# GSH_Bed_V1_0.net
KiCad netlist of a schematic drawn in Altium Designer
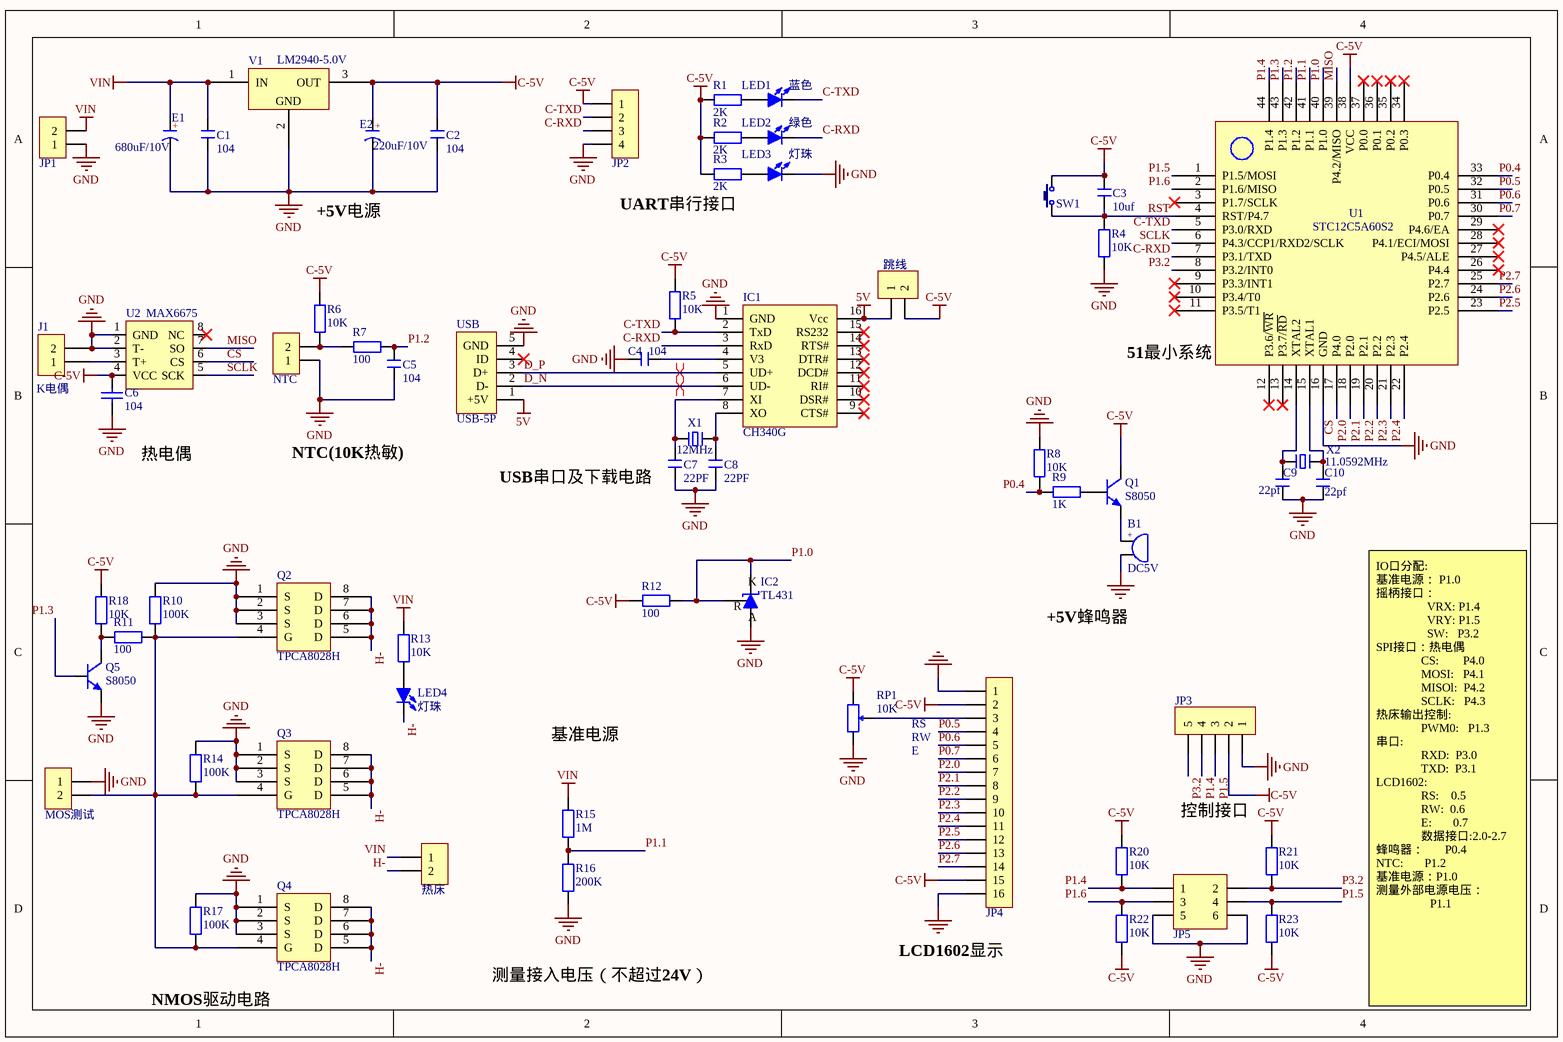
[diagram p0: GSH_Bed_V1.0.SchDoc]

(export (version "E")
  (design (tool "Eeschema 10.0.6"))
  (components
    (comp (ref "B1")
      (value "DC5V")
      (footprint "Buzzer")
      (description "蜂鸣器")
      (fields (field (name "版权归属") "源创客"))
      (libsource (lib "未分类器件") (part "BEEP"))
    )
    (comp (ref "C1")
      (value "104")
      (footprint "C 0805")
      (description "无极性贴片电容")
      (fields (field (name "版权归属") "源创客"))
      (libsource (lib "电阻-电容-电感") (part "C"))
    )
    (comp (ref "C2")
      (value "104")
      (footprint "C 0805")
      (description "无极性贴片电容")
      (fields (field (name "版权归属") "源创客"))
      (libsource (lib "电阻-电容-电感") (part "C"))
    )
    (comp (ref "C3")
      (value "10uf")
      (footprint "C 0603")
      (description "无极性贴片电容")
      (fields (field (name "版权归属") "源创客"))
      (libsource (lib "电阻-电容-电感") (part "C"))
    )
    (comp (ref "C4")
      (value "104")
      (footprint "C 0603")
      (description "无极性贴片电容")
      (fields (field (name "版权归属") "源创客"))
      (libsource (lib "电阻-电容-电感") (part "C"))
    )
    (comp (ref "C5")
      (value "104")
      (footprint "C 0603")
      (description "无极性贴片电容")
      (fields (field (name "版权归属") "源创客"))
      (libsource (lib "电阻-电容-电感") (part "C"))
    )
    (comp (ref "C6")
      (value "104")
      (footprint "C 0603")
      (description "Capacitor")
      (fields (field (name "PUBLISHER") "Altium Limited"))
      (libsource (lib "Miscellaneous Devices") (part "Cap"))
    )
    (comp (ref "C7")
      (value "22PF")
      (footprint "C 0603")
      (description "无极性贴片电容")
      (fields (field (name "版权归属") "源创客"))
      (libsource (lib "电阻-电容-电感") (part "C"))
    )
    (comp (ref "C8")
      (value "22PF")
      (footprint "C 0603")
      (description "无极性贴片电容")
      (fields (field (name "版权归属") "源创客"))
      (libsource (lib "电阻-电容-电感") (part "C"))
    )
    (comp (ref "C9")
      (value "22pf")
      (footprint "C 0603")
      (description "无极性贴片电容")
      (fields (field (name "版权归属") "源创客"))
      (libsource (lib "电阻-电容-电感") (part "C"))
    )
    (comp (ref "C10")
      (value "22pf")
      (footprint "C 0603")
      (description "无极性贴片电容")
      (fields (field (name "版权归属") "源创客"))
      (libsource (lib "电阻-电容-电感") (part "C"))
    )
    (comp (ref "E1")
      (value "680uF/10V")
      (footprint "CM F(10*10.2)")
      (description "贴片电解电容")
      (fields (field (name "版权归属") "源创客"))
      (libsource (lib "电阻-电容-电感") (part "C-CM"))
    )
    (comp (ref "E2")
      (value "220uF/10V")
      (footprint "CM D(6.3*5.4)")
      (description "贴片电解电容")
      (fields (field (name "版权归属") "源创客"))
      (libsource (lib "电阻-电容-电感") (part "C-CM"))
    )
    (comp (ref "IC1")
      (value "CH340G")
      (footprint "SOP16_N")
      (description "串口转USB")
      (fields (field (name "版权归属") "源创客"))
      (libsource (lib "IC芯片") (part "CH340G"))
    )
    (comp (ref "IC2")
      (value "TL431")
      (footprint "SOT23-3L")
      (description "可调基准稳压芯片")
      (fields (field (name "版权归属") "源创客"))
      (libsource (lib "1.3   - 电源类芯片") (part "TL431-ID"))
    )
    (comp (ref "J1")
      (value "K电偶")
      (footprint "HDR-1x2")
      (description "Connector")
      (libsource (lib "lihong_sch") (part "CON2"))
    )
    (comp (ref "JP1")
      (value "HDR-1X2")
      (footprint "KF2EDGK5.0-2P")
      (description "2P接插件")
      (fields (field (name "版权归属") "源创客"))
      (libsource (lib "") (part "Header 2_2"))
    )
    (comp (ref "JP2")
      (value "HDR-1X4")
      (footprint "HDR-1X4")
      (description "4P接插件")
      (fields (field (name "版权归属") "源创客"))
      (libsource (lib "接插件") (part "Header 4"))
    )
    (comp (ref "JP3")
      (value "HDR-1X5")
      (footprint "XH2.54-5P")
      (description "5P接插件")
      (fields (field (name "版权归属") "源创客"))
      (libsource (lib "接插件") (part "Header 5"))
    )
    (comp (ref "JP4")
      (value "HDR-1X16")
      (footprint "LCD-1602")
      (description "16P接插件")
      (fields (field (name "版权归属") "源创客"))
      (libsource (lib "接插件") (part "Header 16"))
    )
    (comp (ref "JP5")
      (value "Header3X2")
      (footprint "HDR-3X2")
      (description "3*2P接插件")
      (fields (field (name "版权归属") "源创客"))
      (libsource (lib "接插件") (part "Header 3X2"))
    )
    (comp (ref "LED1")
      (value "蓝色")
      (footprint "LED 0603B")
      (description "贴片LED")
      (fields (field (name "版权归属") "源创客"))
      (libsource (lib "LED") (part "LED-SMD"))
    )
    (comp (ref "LED2")
      (value "绿色")
      (footprint "LED 0603G")
      (description "贴片LED")
      (fields (field (name "版权归属") "源创客"))
      (libsource (lib "LED") (part "LED-SMD"))
    )
    (comp (ref "LED3")
      (value "灯珠")
      (footprint "LED 3MM-R")
      (description "3mm-LED")
      (fields (field (name "版权归属") "源创客"))
      (libsource (lib "LED") (part "LED-SMD"))
    )
    (comp (ref "LED4")
      (value "灯珠")
      (footprint "LED 3MM-R")
      (description "3mm-LED")
      (fields (field (name "版权归属") "源创客"))
      (libsource (lib "LED") (part "LED-SMD"))
    )
    (comp (ref "MOS测试")
      (value "HDR-1X2")
      (footprint "HDR-1X2")
      (description "2P接插件")
      (fields (field (name "版权归属") "源创客"))
      (libsource (lib "接插件") (part "Header 2"))
    )
    (comp (ref "NTC")
      (value "HDR-1X2")
      (footprint "XH2.54-2P")
      (description "2P接插件")
      (fields (field (name "版权归属") "源创客"))
      (libsource (lib "") (part "Header 2_2"))
    )
    (comp (ref "Q1")
      (value "S8050")
      (footprint "SOT23-3N")
      (description "高频放大-NPN型")
      (fields (field (name "版权归属") "源创客"))
      (libsource (lib "三极管") (part "8050-SMD"))
    )
    (comp (ref "Q2")
      (value "TPCA8028H")
      (footprint "MOS")
      (description "n-mos")
      (libsource (lib "stc12c5a60s2") (part "AON7544"))
    )
    (comp (ref "Q3")
      (value "TPCA8028H")
      (footprint "MOS")
      (description "n-mos")
      (libsource (lib "stc12c5a60s2") (part "AON7544"))
    )
    (comp (ref "Q4")
      (value "TPCA8028H")
      (footprint "MOS")
      (description "n-mos")
      (libsource (lib "stc12c5a60s2") (part "AON7544"))
    )
    (comp (ref "Q5")
      (value "S8050")
      (footprint "SOT23-3N")
      (description "高频放大-NPN型")
      (fields (field (name "版权归属") "源创客"))
      (libsource (lib "三极管") (part "8050-SMD"))
    )
    (comp (ref "R1")
      (value "2K")
      (footprint "R 0603-HP")
      (description "贴片电阻")
      (fields (field (name "版权归属") "源创客"))
      (libsource (lib "电阻-电容-电感") (part "R"))
    )
    (comp (ref "R2")
      (value "2K")
      (footprint "R 0603-HP")
      (description "贴片电阻")
      (fields (field (name "版权归属") "源创客"))
      (libsource (lib "电阻-电容-电感") (part "R"))
    )
    (comp (ref "R3")
      (value "2K")
      (footprint "R 0603-HP")
      (description "贴片电阻")
      (fields (field (name "版权归属") "源创客"))
      (libsource (lib "电阻-电容-电感") (part "R"))
    )
    (comp (ref "R4")
      (value "10K")
      (footprint "R 0603-HP")
      (description "贴片电阻")
      (fields (field (name "版权归属") "源创客"))
      (libsource (lib "电阻-电容-电感") (part "R"))
    )
    (comp (ref "R5")
      (value "10K")
      (footprint "R 0603-HP")
      (description "贴片电阻")
      (fields (field (name "版权归属") "源创客"))
      (libsource (lib "电阻-电容-电感") (part "R"))
    )
    (comp (ref "R6")
      (value "10K")
      (footprint "R 0603-HP")
      (description "贴片电阻")
      (fields (field (name "版权归属") "源创客"))
      (libsource (lib "电阻-电容-电感") (part "R"))
    )
    (comp (ref "R7")
      (value "100")
      (footprint "R 0603-HP")
      (description "贴片电阻")
      (fields (field (name "版权归属") "源创客"))
      (libsource (lib "电阻-电容-电感") (part "R"))
    )
    (comp (ref "R8")
      (value "10K")
      (footprint "R 0603-HP")
      (description "贴片电阻")
      (fields (field (name "版权归属") "源创客"))
      (libsource (lib "电阻-电容-电感") (part "R"))
    )
    (comp (ref "R9")
      (value "1K")
      (footprint "R 0603-HP")
      (description "贴片电阻")
      (fields (field (name "版权归属") "源创客"))
      (libsource (lib "电阻-电容-电感") (part "R"))
    )
    (comp (ref "R10")
      (value "100K")
      (footprint "R 0603-HP")
      (description "贴片电阻")
      (fields (field (name "版权归属") "源创客"))
      (libsource (lib "电阻-电容-电感") (part "R"))
    )
    (comp (ref "R11")
      (value "100")
      (footprint "R 0603-HP")
      (description "贴片电阻")
      (fields (field (name "版权归属") "源创客"))
      (libsource (lib "电阻-电容-电感") (part "R"))
    )
    (comp (ref "R12")
      (value "100")
      (footprint "R 0603-HP")
      (description "贴片电阻")
      (fields (field (name "版权归属") "源创客"))
      (libsource (lib "电阻-电容-电感") (part "R"))
    )
    (comp (ref "R13")
      (value "10K")
      (footprint "R 0603-HP")
      (description "贴片电阻")
      (fields (field (name "版权归属") "源创客"))
      (libsource (lib "电阻-电容-电感") (part "R"))
    )
    (comp (ref "R14")
      (value "100K")
      (footprint "R 0603-HP")
      (description "贴片电阻")
      (fields (field (name "版权归属") "源创客"))
      (libsource (lib "电阻-电容-电感") (part "R"))
    )
    (comp (ref "R15")
      (value "1M")
      (footprint "R 0603-HP")
      (description "贴片电阻")
      (fields (field (name "版权归属") "源创客"))
      (libsource (lib "电阻-电容-电感") (part "R"))
    )
    (comp (ref "R16")
      (value "200K")
      (footprint "R 0603-HP")
      (description "贴片电阻")
      (fields (field (name "版权归属") "源创客"))
      (libsource (lib "电阻-电容-电感") (part "R"))
    )
    (comp (ref "R17")
      (value "100K")
      (footprint "R 0603-HP")
      (description "贴片电阻")
      (fields (field (name "版权归属") "源创客"))
      (libsource (lib "电阻-电容-电感") (part "R"))
    )
    (comp (ref "R18")
      (value "10K")
      (footprint "R 0603-HP")
      (description "贴片电阻")
      (fields (field (name "版权归属") "源创客"))
      (libsource (lib "电阻-电容-电感") (part "R"))
    )
    (comp (ref "R20")
      (value "10K")
      (footprint "R 0603-HP")
      (description "贴片电阻")
      (fields (field (name "版权归属") "源创客"))
      (libsource (lib "电阻-电容-电感") (part "R"))
    )
    (comp (ref "R21")
      (value "10K")
      (footprint "R 0603-HP")
      (description "贴片电阻")
      (fields (field (name "版权归属") "源创客"))
      (libsource (lib "电阻-电容-电感") (part "R"))
    )
    (comp (ref "R22")
      (value "10K")
      (footprint "R 0603-HP")
      (description "贴片电阻")
      (fields (field (name "版权归属") "源创客"))
      (libsource (lib "电阻-电容-电感") (part "R"))
    )
    (comp (ref "R23")
      (value "10K")
      (footprint "R 0603-HP")
      (description "贴片电阻")
      (fields (field (name "版权归属") "源创客"))
      (libsource (lib "电阻-电容-电感") (part "R"))
    )
    (comp (ref "RP1")
      (value "10K")
      (footprint "RM065")
      (description "插件单联电位器")
      (fields (field (name "版权归属") "源创客"))
      (libsource (lib "电阻-电容-电感") (part "RP-ID"))
    )
    (comp (ref "SW1")
      (value "3x6x5")
      (footprint "TSW SMD-3*6*2.5")
      (description "3x6轻触开关")
      (fields (field (name "版权归属") "源创客"))
      (libsource (lib "按键-开关") (part "TSW 3x6"))
    )
    (comp (ref "U1")
      (value "STC12C5A60S2")
      (footprint "LQFP44 10X10_L")
      (libsource (lib "stc12c5a60s2") (part "U?"))
    )
    (comp (ref "U2")
      (value "MAX6675")
      (footprint "SOP8_L")
      (description "K电偶转换")
      (libsource (lib "lihong_IC") (part "MAX6675"))
    )
    (comp (ref "USB")
      (value "USB-5P")
      (footprint "USB-MICRO_A")
      (description "微型USB母座")
      (fields (field (name "版权归属") "源创客"))
      (libsource (lib "接口类") (part "USB-5P"))
    )
    (comp (ref "V1")
      (value "LM2940-5.0V")
      (footprint "TO252")
      (description "5V稳压芯片")
      (fields (field (name "版权归属") "源创客"))
      (libsource (lib "IC芯片") (part "LM2940"))
    )
    (comp (ref "X1")
      (value "12MHz")
      (footprint "XTAL-49S DIP")
      (description "2脚晶振")
      (fields (field (name "版权归属") "源创客"))
      (libsource (lib "保险丝-晶振") (part "XTAL-2"))
    )
    (comp (ref "X2")
      (value "11.0592MHz")
      (footprint "XTAL-49S DIP")
      (description "2脚晶振")
      (fields (field (name "版权归属") "源创客"))
      (libsource (lib "保险丝-晶振") (part "XTAL-2"))
    )
    (comp (ref "热床")
      (value "HDR-1X2")
      (footprint "KF2EDGK5.0-2P")
      (description "2P接插件")
      (fields (field (name "版权归属") "源创客"))
      (libsource (lib "") (part "Header 2_1"))
    )
    (comp (ref "跳线")
      (value "HDR-1X2")
      (footprint "HDR-1X2")
      (description "2P接插件")
      (fields (field (name "版权归属") "源创客"))
      (libsource (lib "") (part "Header 2_3"))
    )
  )
  (nets
    (net (code "1") (name "/C-RXD") (class "Default")
      (node (ref "IC1") (pin "3") (pinfunction "RxD_3") (pintype "passive"))
      (node (ref "JP2") (pin "3") (pinfunction "3_3") (pintype "passive"))
      (node (ref "LED2") (pin "2") (pinfunction "K_2") (pintype "passive"))
      (node (ref "U1") (pin "7") (pinfunction "P3.1/TXD_7") (pintype "passive"))
    )
    (net (code "2") (name "/C-TXD") (class "Default")
      (node (ref "IC1") (pin "2") (pinfunction "TxD_2") (pintype "passive"))
      (node (ref "JP2") (pin "2") (pinfunction "2_2") (pintype "passive"))
      (node (ref "LED1") (pin "2") (pinfunction "K_2") (pintype "passive"))
      (node (ref "R5") (pin "1") (pinfunction "1_1") (pintype "passive"))
      (node (ref "U1") (pin "5") (pinfunction "P3.0/RXD_5") (pintype "passive"))
    )
    (net (code "3") (name "/CS") (class "Default")
      (node (ref "U1") (pin "17") (pinfunction "P4.0_17") (pintype "passive"))
      (node (ref "U2") (pin "6") (pinfunction "CS_6") (pintype "passive"))
    )
    (net (code "4") (name "/D_N") (class "Default")
      (node (ref "IC1") (pin "6") (pinfunction "UD-_6") (pintype "passive"))
      (node (ref "USB") (pin "2") (pinfunction "D-_2") (pintype "passive"))
    )
    (net (code "5") (name "/D_P") (class "Default")
      (node (ref "IC1") (pin "5") (pinfunction "UD+_5") (pintype "passive"))
      (node (ref "USB") (pin "3") (pinfunction "D+_3") (pintype "passive"))
    )
    (net (code "6") (name "/H-") (class "Default")
      (node (ref "LED4") (pin "2") (pinfunction "K_2") (pintype "passive"))
      (node (ref "Q2") (pin "5") (pinfunction "D_5") (pintype "passive"))
      (node (ref "Q2") (pin "6") (pinfunction "D_6") (pintype "passive"))
      (node (ref "Q2") (pin "7") (pinfunction "D_7") (pintype "passive"))
      (node (ref "Q2") (pin "8") (pinfunction "D_8") (pintype "passive"))
      (node (ref "Q3") (pin "5") (pinfunction "D_5") (pintype "passive"))
      (node (ref "Q3") (pin "6") (pinfunction "D_6") (pintype "passive"))
      (node (ref "Q3") (pin "7") (pinfunction "D_7") (pintype "passive"))
      (node (ref "Q3") (pin "8") (pinfunction "D_8") (pintype "passive"))
      (node (ref "Q4") (pin "5") (pinfunction "D_5") (pintype "passive"))
      (node (ref "Q4") (pin "6") (pinfunction "D_6") (pintype "passive"))
      (node (ref "Q4") (pin "7") (pinfunction "D_7") (pintype "passive"))
      (node (ref "Q4") (pin "8") (pinfunction "D_8") (pintype "passive"))
      (node (ref "热床") (pin "2") (pinfunction "2_2") (pintype "passive"))
    )
    (net (code "7") (name "/MISO") (class "Default")
      (node (ref "U1") (pin "39") (pinfunction "P4.2/MISO_39") (pintype "passive"))
      (node (ref "U2") (pin "7") (pinfunction "SO_7") (pintype "passive"))
    )
    (net (code "8") (name "/P0.4") (class "Default")
      (node (ref "R8") (pin "2") (pinfunction "2_2") (pintype "passive"))
      (node (ref "R9") (pin "1") (pinfunction "1_1") (pintype "passive"))
      (node (ref "U1") (pin "33") (pinfunction "P0.4_33") (pintype "passive"))
    )
    (net (code "9") (name "/P0.5") (class "Default")
      (node (ref "JP4") (pin "4") (pinfunction "4_4") (pintype "passive"))
      (node (ref "U1") (pin "32") (pinfunction "P0.5_32") (pintype "passive"))
    )
    (net (code "10") (name "/P0.6") (class "Default")
      (node (ref "JP4") (pin "5") (pinfunction "5_5") (pintype "passive"))
      (node (ref "U1") (pin "31") (pinfunction "P0.6_31") (pintype "passive"))
    )
    (net (code "11") (name "/P0.7") (class "Default")
      (node (ref "JP4") (pin "6") (pinfunction "6_6") (pintype "passive"))
      (node (ref "U1") (pin "30") (pinfunction "P0.7_30") (pintype "passive"))
    )
    (net (code "12") (name "/P1.0") (class "Default")
      (node (ref "IC2") (pin "1") (pinfunction "R_1") (pintype "passive"))
      (node (ref "IC2") (pin "2") (pinfunction "K_2") (pintype "passive"))
      (node (ref "R12") (pin "1") (pinfunction "1_1") (pintype "passive"))
      (node (ref "U1") (pin "40") (pinfunction "P1.0_40") (pintype "passive"))
    )
    (net (code "13") (name "/P1.1") (class "Default")
      (node (ref "R15") (pin "1") (pinfunction "1_1") (pintype "passive"))
      (node (ref "R16") (pin "2") (pinfunction "2_2") (pintype "passive"))
      (node (ref "U1") (pin "41") (pinfunction "P1.1_41") (pintype "passive"))
    )
    (net (code "14") (name "/P1.2") (class "Default")
      (node (ref "C5") (pin "2") (pinfunction "2_2") (pintype "passive"))
      (node (ref "R7") (pin "1") (pinfunction "1_1") (pintype "passive"))
      (node (ref "U1") (pin "42") (pinfunction "P1.2_42") (pintype "passive"))
    )
    (net (code "15") (name "/P1.3") (class "Default")
      (node (ref "Q5") (pin "1") (pinfunction "B_1") (pintype "passive"))
      (node (ref "U1") (pin "43") (pinfunction "P1.3_43") (pintype "passive"))
    )
    (net (code "16") (name "/P1.4") (class "Default")
      (node (ref "JP3") (pin "4") (pinfunction "4_4") (pintype "passive"))
      (node (ref "JP5") (pin "1") (pinfunction "1_1") (pintype "passive"))
      (node (ref "R20") (pin "1") (pinfunction "1_1") (pintype "passive"))
      (node (ref "U1") (pin "44") (pinfunction "P1.4_44") (pintype "passive"))
    )
    (net (code "17") (name "/P1.5") (class "Default")
      (node (ref "JP3") (pin "3") (pinfunction "3_3") (pintype "passive"))
      (node (ref "JP5") (pin "4") (pinfunction "4_4") (pintype "passive"))
      (node (ref "R23") (pin "2") (pinfunction "2_2") (pintype "passive"))
      (node (ref "U1") (pin "1") (pinfunction "P1.5/MOSI_1") (pintype "passive"))
    )
    (net (code "18") (name "/P1.6") (class "Default")
      (node (ref "JP5") (pin "3") (pinfunction "3_3") (pintype "passive"))
      (node (ref "R22") (pin "2") (pinfunction "2_2") (pintype "passive"))
      (node (ref "U1") (pin "2") (pinfunction "P1.6/MISO_2") (pintype "passive"))
    )
    (net (code "19") (name "/P2.0") (class "Default")
      (node (ref "JP4") (pin "7") (pinfunction "7_7") (pintype "passive"))
      (node (ref "U1") (pin "18") (pinfunction "P2.0_18") (pintype "passive"))
    )
    (net (code "20") (name "/P2.1") (class "Default")
      (node (ref "JP4") (pin "8") (pinfunction "8_8") (pintype "passive"))
      (node (ref "U1") (pin "19") (pinfunction "P2.1_19") (pintype "passive"))
    )
    (net (code "21") (name "/P2.2") (class "Default")
      (node (ref "JP4") (pin "9") (pinfunction "9_9") (pintype "passive"))
      (node (ref "U1") (pin "20") (pinfunction "P2.2_20") (pintype "passive"))
    )
    (net (code "22") (name "/P2.3") (class "Default")
      (node (ref "JP4") (pin "10") (pinfunction "10_10") (pintype "passive"))
      (node (ref "U1") (pin "21") (pinfunction "P2.3_21") (pintype "passive"))
    )
    (net (code "23") (name "/P2.4") (class "Default")
      (node (ref "JP4") (pin "11") (pinfunction "11_11") (pintype "passive"))
      (node (ref "U1") (pin "22") (pinfunction "P2.4_22") (pintype "passive"))
    )
    (net (code "24") (name "/P2.5") (class "Default")
      (node (ref "JP4") (pin "12") (pinfunction "12_12") (pintype "passive"))
      (node (ref "U1") (pin "23") (pinfunction "P2.5_23") (pintype "passive"))
    )
    (net (code "25") (name "/P2.6") (class "Default")
      (node (ref "JP4") (pin "13") (pinfunction "13_13") (pintype "passive"))
      (node (ref "U1") (pin "24") (pinfunction "P2.6_24") (pintype "passive"))
    )
    (net (code "26") (name "/P2.7") (class "Default")
      (node (ref "JP4") (pin "14") (pinfunction "14_14") (pintype "passive"))
      (node (ref "U1") (pin "25") (pinfunction "P2.7_25") (pintype "passive"))
    )
    (net (code "27") (name "/P3.2") (class "Default")
      (node (ref "JP3") (pin "5") (pinfunction "5_5") (pintype "passive"))
      (node (ref "JP5") (pin "2") (pinfunction "2_2") (pintype "passive"))
      (node (ref "R21") (pin "1") (pinfunction "1_1") (pintype "passive"))
      (node (ref "U1") (pin "8") (pinfunction "P3.2/INT0_8") (pintype "passive"))
    )
    (net (code "28") (name "/RST") (class "Default")
      (node (ref "C3") (pin "1") (pinfunction "1_1") (pintype "passive"))
      (node (ref "R4") (pin "2") (pinfunction "2_2") (pintype "passive"))
      (node (ref "SW1") (pin "1") (pinfunction "1_1") (pintype "passive"))
      (node (ref "U1") (pin "4") (pinfunction "RST/P4.7_4") (pintype "passive"))
    )
    (net (code "29") (name "/SCLK") (class "Default")
      (node (ref "U1") (pin "6") (pinfunction "P4.3/CCP1/RXD2/SCLK_6") (pintype "passive"))
      (node (ref "U2") (pin "5") (pinfunction "SCK_5") (pintype "passive"))
    )
    (net (code "30") (name "5V") (class "Default")
      (node (ref "IC1") (pin "16") (pinfunction "Vcc_16") (pintype "passive"))
      (node (ref "USB") (pin "1") (pinfunction "+5V_1") (pintype "passive"))
      (node (ref "跳线") (pin "1") (pinfunction "1_1") (pintype "passive"))
    )
    (net (code "31") (name "C-5V") (class "Default")
      (node (ref "C2") (pin "2") (pinfunction "2_2") (pintype "passive"))
      (node (ref "C3") (pin "2") (pinfunction "2_2") (pintype "passive"))
      (node (ref "C6") (pin "2") (pinfunction "2_2") (pintype "passive"))
      (node (ref "E2") (pin "1") (pinfunction "A_1") (pintype "passive"))
      (node (ref "JP2") (pin "1") (pinfunction "1_1") (pintype "passive"))
      (node (ref "JP3") (pin "2") (pinfunction "2_2") (pintype "passive"))
      (node (ref "JP4") (pin "15") (pinfunction "15_15") (pintype "passive"))
      (node (ref "JP4") (pin "2") (pinfunction "2_2") (pintype "passive"))
      (node (ref "Q1") (pin "3") (pinfunction "C_3") (pintype "passive"))
      (node (ref "R1") (pin "2") (pinfunction "2_2") (pintype "passive"))
      (node (ref "R12") (pin "2") (pinfunction "2_2") (pintype "passive"))
      (node (ref "R18") (pin "2") (pinfunction "2_2") (pintype "passive"))
      (node (ref "R2") (pin "2") (pinfunction "2_2") (pintype "passive"))
      (node (ref "R20") (pin "2") (pinfunction "2_2") (pintype "passive"))
      (node (ref "R21") (pin "2") (pinfunction "2_2") (pintype "passive"))
      (node (ref "R22") (pin "1") (pinfunction "1_1") (pintype "passive"))
      (node (ref "R23") (pin "1") (pinfunction "1_1") (pintype "passive"))
      (node (ref "R3") (pin "2") (pinfunction "2_2") (pintype "passive"))
      (node (ref "R5") (pin "2") (pinfunction "2_2") (pintype "passive"))
      (node (ref "R6") (pin "2") (pinfunction "2_2") (pintype "passive"))
      (node (ref "RP1") (pin "1") (pinfunction "1_1") (pintype "passive"))
      (node (ref "SW1") (pin "2") (pinfunction "2_2") (pintype "passive"))
      (node (ref "U1") (pin "38") (pinfunction "VCC_38") (pintype "passive"))
      (node (ref "U2") (pin "4") (pinfunction "VCC_4") (pintype "passive"))
      (node (ref "V1") (pin "3") (pinfunction "OUT_3") (pintype "power_in"))
      (node (ref "跳线") (pin "2") (pinfunction "2_2") (pintype "passive"))
    )
    (net (code "32") (name "GND") (class "Default")
      (node (ref "B1") (pin "2") (pinfunction "2_2") (pintype "passive"))
      (node (ref "C1") (pin "1") (pinfunction "1_1") (pintype "passive"))
      (node (ref "C10") (pin "1") (pinfunction "1_1") (pintype "passive"))
      (node (ref "C2") (pin "1") (pinfunction "1_1") (pintype "passive"))
      (node (ref "C4") (pin "1") (pinfunction "1_1") (pintype "passive"))
      (node (ref "C5") (pin "1") (pinfunction "1_1") (pintype "passive"))
      (node (ref "C6") (pin "1") (pinfunction "1_1") (pintype "passive"))
      (node (ref "C7") (pin "2") (pinfunction "2_2") (pintype "passive"))
      (node (ref "C8") (pin "2") (pinfunction "2_2") (pintype "passive"))
      (node (ref "C9") (pin "1") (pinfunction "1_1") (pintype "passive"))
      (node (ref "E1") (pin "2") (pinfunction "K_2") (pintype "passive"))
      (node (ref "E2") (pin "2") (pinfunction "K_2") (pintype "passive"))
      (node (ref "IC1") (pin "1") (pinfunction "GND_1") (pintype "passive"))
      (node (ref "IC2") (pin "3") (pinfunction "A_3") (pintype "passive"))
      (node (ref "J1") (pin "2") (pinfunction "2_2") (pintype "passive"))
      (node (ref "JP1") (pin "1") (pinfunction "1_1") (pintype "passive"))
      (node (ref "JP2") (pin "4") (pinfunction "4_4") (pintype "passive"))
      (node (ref "JP3") (pin "1") (pinfunction "1_1") (pintype "passive"))
      (node (ref "JP4") (pin "1") (pinfunction "1_1") (pintype "passive"))
      (node (ref "JP4") (pin "16") (pinfunction "16_16") (pintype "passive"))
      (node (ref "JP5") (pin "5") (pinfunction "5_5") (pintype "passive"))
      (node (ref "JP5") (pin "6") (pinfunction "6_6") (pintype "passive"))
      (node (ref "LED3") (pin "2") (pinfunction "K_2") (pintype "passive"))
      (node (ref "MOS测试") (pin "1") (pinfunction "1_1") (pintype "passive"))
      (node (ref "NTC") (pin "1") (pinfunction "1_1") (pintype "passive"))
      (node (ref "Q2") (pin "1") (pinfunction "S_1") (pintype "passive"))
      (node (ref "Q2") (pin "2") (pinfunction "S_2") (pintype "passive"))
      (node (ref "Q2") (pin "3") (pinfunction "S_3") (pintype "passive"))
      (node (ref "Q3") (pin "1") (pinfunction "S_1") (pintype "passive"))
      (node (ref "Q3") (pin "2") (pinfunction "S_2") (pintype "passive"))
      (node (ref "Q3") (pin "3") (pinfunction "S_3") (pintype "passive"))
      (node (ref "Q4") (pin "1") (pinfunction "S_1") (pintype "passive"))
      (node (ref "Q4") (pin "2") (pinfunction "S_2") (pintype "passive"))
      (node (ref "Q4") (pin "3") (pinfunction "S_3") (pintype "passive"))
      (node (ref "Q5") (pin "2") (pinfunction "E_2") (pintype "passive"))
      (node (ref "R10") (pin "2") (pinfunction "2_2") (pintype "passive"))
      (node (ref "R14") (pin "2") (pinfunction "2_2") (pintype "passive"))
      (node (ref "R16") (pin "1") (pinfunction "1_1") (pintype "passive"))
      (node (ref "R17") (pin "2") (pinfunction "2_2") (pintype "passive"))
      (node (ref "R4") (pin "1") (pinfunction "1_1") (pintype "passive"))
      (node (ref "R8") (pin "1") (pinfunction "1_1") (pintype "passive"))
      (node (ref "RP1") (pin "3") (pinfunction "3_3") (pintype "passive"))
      (node (ref "U1") (pin "16") (pinfunction "GND_16") (pintype "passive"))
      (node (ref "U2") (pin "1") (pinfunction "GND_1") (pintype "passive"))
      (node (ref "U2") (pin "2") (pinfunction "T-_2") (pintype "passive"))
      (node (ref "USB") (pin "5") (pinfunction "GND_5") (pintype "passive"))
      (node (ref "V1") (pin "2") (pinfunction "GND_2") (pintype "power_in"))
    )
    (net (code "33") (name "Net-(IC1-V3)") (class "Default")
      (node (ref "C4") (pin "2") (pinfunction "2_2") (pintype "passive"))
      (node (ref "IC1") (pin "4") (pinfunction "V3_4") (pintype "passive"))
    )
    (net (code "34") (name "Net-(IC1-XI)") (class "Default")
      (node (ref "C7") (pin "1") (pinfunction "1_1") (pintype "passive"))
      (node (ref "IC1") (pin "7") (pinfunction "XI_7") (pintype "passive"))
      (node (ref "X1") (pin "1") (pinfunction "1_1") (pintype "passive"))
    )
    (net (code "35") (name "Net-(IC1-XO)") (class "Default")
      (node (ref "C8") (pin "1") (pinfunction "1_1") (pintype "passive"))
      (node (ref "IC1") (pin "8") (pinfunction "XO_8") (pintype "passive"))
      (node (ref "X1") (pin "2") (pinfunction "2_2") (pintype "passive"))
    )
    (net (code "36") (name "Net-(JP4-Pad3)") (class "Default")
      (node (ref "JP4") (pin "3") (pinfunction "3_3") (pintype "passive"))
      (node (ref "RP1") (pin "2") (pinfunction "2_2") (pintype "passive"))
    )
    (net (code "37") (name "Net-(LED1-A)") (class "Default")
      (node (ref "LED1") (pin "1") (pinfunction "A_1") (pintype "passive"))
      (node (ref "R1") (pin "1") (pinfunction "1_1") (pintype "passive"))
    )
    (net (code "38") (name "Net-(LED2-A)") (class "Default")
      (node (ref "LED2") (pin "1") (pinfunction "A_1") (pintype "passive"))
      (node (ref "R2") (pin "1") (pinfunction "1_1") (pintype "passive"))
    )
    (net (code "39") (name "Net-(LED3-A)") (class "Default")
      (node (ref "LED3") (pin "1") (pinfunction "A_1") (pintype "passive"))
      (node (ref "R3") (pin "1") (pinfunction "1_1") (pintype "passive"))
    )
    (net (code "40") (name "Net-(LED4-A)") (class "Default")
      (node (ref "LED4") (pin "1") (pinfunction "A_1") (pintype "passive"))
      (node (ref "R13") (pin "1") (pinfunction "1_1") (pintype "passive"))
    )
    (net (code "41") (name "Net-(NTC-Pad2)") (class "Default")
      (node (ref "NTC") (pin "2") (pinfunction "2_2") (pintype "passive"))
      (node (ref "R6") (pin "1") (pinfunction "1_1") (pintype "passive"))
      (node (ref "R7") (pin "2") (pinfunction "2_2") (pintype "passive"))
    )
    (net (code "42") (name "Net-(Q1-B)") (class "Default")
      (node (ref "Q1") (pin "1") (pinfunction "B_1") (pintype "passive"))
      (node (ref "R9") (pin "2") (pinfunction "2_2") (pintype "passive"))
    )
    (net (code "43") (name "Net-(Q1-E)") (class "Default")
      (node (ref "B1") (pin "1") (pinfunction "1_1") (pintype "passive"))
      (node (ref "Q1") (pin "2") (pinfunction "E_2") (pintype "passive"))
    )
    (net (code "44") (name "Net-(Q2-G)") (class "Default")
      (node (ref "MOS测试") (pin "2") (pinfunction "2_2") (pintype "passive"))
      (node (ref "Q2") (pin "4") (pinfunction "G_4") (pintype "passive"))
      (node (ref "Q3") (pin "4") (pinfunction "G_4") (pintype "passive"))
      (node (ref "Q4") (pin "4") (pinfunction "G_4") (pintype "passive"))
      (node (ref "R10") (pin "1") (pinfunction "1_1") (pintype "passive"))
      (node (ref "R11") (pin "2") (pinfunction "2_2") (pintype "passive"))
      (node (ref "R14") (pin "1") (pinfunction "1_1") (pintype "passive"))
      (node (ref "R17") (pin "1") (pinfunction "1_1") (pintype "passive"))
    )
    (net (code "45") (name "Net-(Q5-C)") (class "Default")
      (node (ref "Q5") (pin "3") (pinfunction "C_3") (pintype "passive"))
      (node (ref "R11") (pin "1") (pinfunction "1_1") (pintype "passive"))
      (node (ref "R18") (pin "1") (pinfunction "1_1") (pintype "passive"))
    )
    (net (code "46") (name "Net-(U1-XTAL1)") (class "Default")
      (node (ref "C10") (pin "2") (pinfunction "2_2") (pintype "passive"))
      (node (ref "U1") (pin "15") (pinfunction "XTAL1_15") (pintype "passive"))
      (node (ref "X2") (pin "1") (pinfunction "1_1") (pintype "passive"))
    )
    (net (code "47") (name "Net-(U1-XTAL2)") (class "Default")
      (node (ref "C9") (pin "2") (pinfunction "2_2") (pintype "passive"))
      (node (ref "U1") (pin "14") (pinfunction "XTAL2_14") (pintype "passive"))
      (node (ref "X2") (pin "2") (pinfunction "2_2") (pintype "passive"))
    )
    (net (code "48") (name "Net-(U2-T+)") (class "Default")
      (node (ref "J1") (pin "1") (pinfunction "1_1") (pintype "passive"))
      (node (ref "U2") (pin "3") (pinfunction "T+_3") (pintype "passive"))
    )
    (net (code "49") (name "VIN") (class "Default")
      (node (ref "C1") (pin "2") (pinfunction "2_2") (pintype "passive"))
      (node (ref "E1") (pin "1") (pinfunction "A_1") (pintype "passive"))
      (node (ref "JP1") (pin "2") (pinfunction "2_2") (pintype "passive"))
      (node (ref "R13") (pin "2") (pinfunction "2_2") (pintype "passive"))
      (node (ref "R15") (pin "2") (pinfunction "2_2") (pintype "passive"))
      (node (ref "V1") (pin "1") (pinfunction "IN_1") (pintype "power_in"))
      (node (ref "热床") (pin "1") (pinfunction "1_1") (pintype "passive"))
    )
    (net (code "50") (name "unconnected-(IC1-CTS#-Pad9)") (class "Default")
      (node (ref "IC1") (pin "9") (pinfunction "CTS#_9") (pintype "passive+no_connect"))
    )
    (net (code "51") (name "unconnected-(IC1-DCD#-Pad12)") (class "Default")
      (node (ref "IC1") (pin "12") (pinfunction "DCD#_12") (pintype "passive+no_connect"))
    )
    (net (code "52") (name "unconnected-(IC1-DSR#-Pad10)") (class "Default")
      (node (ref "IC1") (pin "10") (pinfunction "DSR#_10") (pintype "passive+no_connect"))
    )
    (net (code "53") (name "unconnected-(IC1-DTR#-Pad13)") (class "Default")
      (node (ref "IC1") (pin "13") (pinfunction "DTR#_13") (pintype "passive+no_connect"))
    )
    (net (code "54") (name "unconnected-(IC1-RI#-Pad11)") (class "Default")
      (node (ref "IC1") (pin "11") (pinfunction "RI#_11") (pintype "passive+no_connect"))
    )
    (net (code "55") (name "unconnected-(IC1-RS232-Pad15)") (class "Default")
      (node (ref "IC1") (pin "15") (pinfunction "RS232_15") (pintype "passive+no_connect"))
    )
    (net (code "56") (name "unconnected-(IC1-RTS#-Pad14)") (class "Default")
      (node (ref "IC1") (pin "14") (pinfunction "RTS#_14") (pintype "passive+no_connect"))
    )
    (net (code "57") (name "unconnected-(U1-P0.0-Pad37)") (class "Default")
      (node (ref "U1") (pin "37") (pinfunction "P0.0_37") (pintype "passive+no_connect"))
    )
    (net (code "58") (name "unconnected-(U1-P0.1-Pad36)") (class "Default")
      (node (ref "U1") (pin "36") (pinfunction "P0.1_36") (pintype "passive+no_connect"))
    )
    (net (code "59") (name "unconnected-(U1-P0.2-Pad35)") (class "Default")
      (node (ref "U1") (pin "35") (pinfunction "P0.2_35") (pintype "passive+no_connect"))
    )
    (net (code "60") (name "unconnected-(U1-P0.3-Pad34)") (class "Default")
      (node (ref "U1") (pin "34") (pinfunction "P0.3_34") (pintype "passive+no_connect"))
    )
    (net (code "61") (name "unconnected-(U1-P1.7{slash}SCLK-Pad3)") (class "Default")
      (node (ref "U1") (pin "3") (pinfunction "P1.7/SCLK_3") (pintype "passive+no_connect"))
    )
    (net (code "62") (name "unconnected-(U1-P3.3{slash}INT1-Pad9)") (class "Default")
      (node (ref "U1") (pin "9") (pinfunction "P3.3/INT1_9") (pintype "passive+no_connect"))
    )
    (net (code "63") (name "unconnected-(U1-P3.4{slash}T0-Pad10)") (class "Default")
      (node (ref "U1") (pin "10") (pinfunction "P3.4/T0_10") (pintype "passive+no_connect"))
    )
    (net (code "64") (name "unconnected-(U1-P3.5{slash}T1-Pad11)") (class "Default")
      (node (ref "U1") (pin "11") (pinfunction "P3.5/T1_11") (pintype "passive+no_connect"))
    )
    (net (code "65") (name "unconnected-(U1-P3.6{slash}~{WR}-Pad12)") (class "Default")
      (node (ref "U1") (pin "12") (pinfunction "P3.6/~{WR}_12") (pintype "passive+no_connect"))
    )
    (net (code "66") (name "unconnected-(U1-P3.7{slash}~{RD}-Pad13)") (class "Default")
      (node (ref "U1") (pin "13") (pinfunction "P3.7/~{RD}_13") (pintype "passive+no_connect"))
    )
    (net (code "67") (name "unconnected-(U1-P4.1{slash}ECI{slash}MOSI-Pad28)") (class "Default")
      (node (ref "U1") (pin "28") (pinfunction "P4.1/ECI/MOSI_28") (pintype "passive+no_connect"))
    )
    (net (code "68") (name "unconnected-(U1-P4.4-Pad26)") (class "Default")
      (node (ref "U1") (pin "26") (pinfunction "P4.4_26") (pintype "passive+no_connect"))
    )
    (net (code "69") (name "unconnected-(U1-P4.5{slash}ALE-Pad27)") (class "Default")
      (node (ref "U1") (pin "27") (pinfunction "P4.5/ALE_27") (pintype "passive+no_connect"))
    )
    (net (code "70") (name "unconnected-(U1-P4.6{slash}EA-Pad29)") (class "Default")
      (node (ref "U1") (pin "29") (pinfunction "P4.6/EA_29") (pintype "passive+no_connect"))
    )
    (net (code "71") (name "unconnected-(U2-NC-Pad8)") (class "Default")
      (node (ref "U2") (pin "8") (pinfunction "NC_8") (pintype "passive+no_connect"))
    )
    (net (code "72") (name "unconnected-(USB-ID-Pad4)") (class "Default")
      (node (ref "USB") (pin "4") (pinfunction "ID_4") (pintype "passive+no_connect"))
    )
  )
)
